# drvinput0.net
KiCad netlist of a schematic drawn in Altium Designer
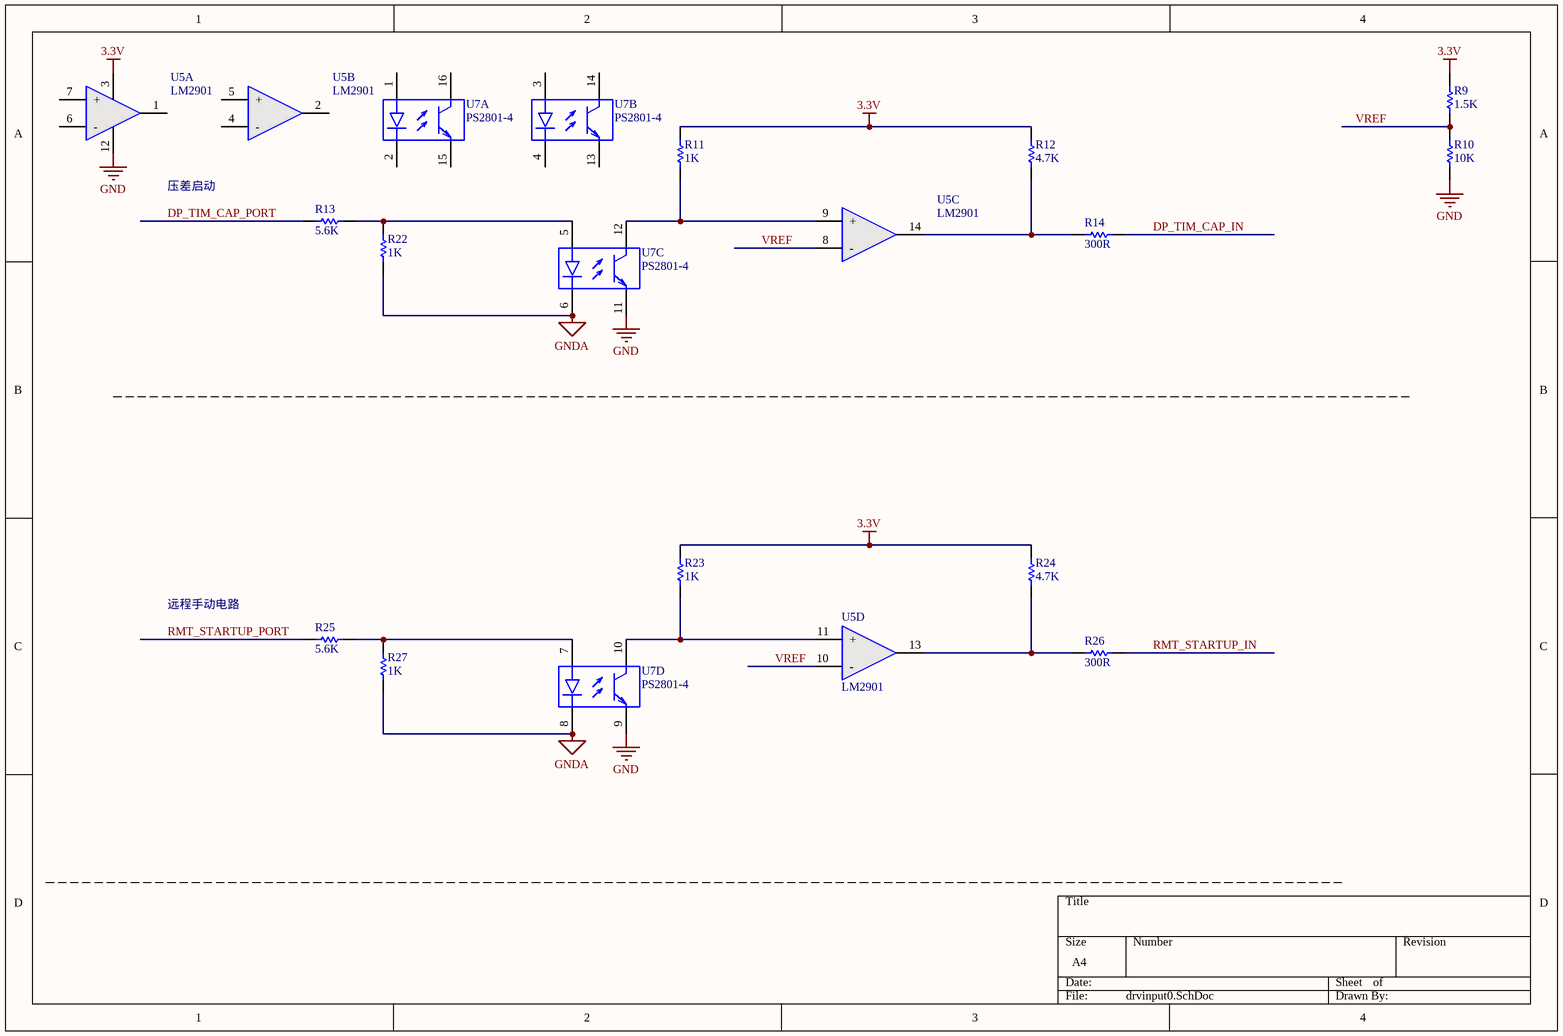
[diagram p0: drvinput0.SchDoc]

(export (version "E")
  (design (tool "Eeschema 10.0.6"))
  (components
    (comp (ref "R9")
      (value "1.5K")
      (footprint "RESC2012M")
      (description "Resistor")
      (fields (field (name "PUBLISHER") "Altium Limited"))
      (libsource (lib "Miscellaneous Devices") (part "Res1"))
    )
    (comp (ref "R10")
      (value "10K")
      (footprint "RESC2012M")
      (description "Resistor")
      (fields (field (name "PUBLISHER") "Altium Limited"))
      (libsource (lib "Miscellaneous Devices") (part "Res1"))
    )
    (comp (ref "R11")
      (value "1K")
      (footprint "RESC2012M")
      (description "Resistor")
      (fields (field (name "PUBLISHER") "Altium Limited"))
      (libsource (lib "Miscellaneous Devices") (part "Res1"))
    )
    (comp (ref "R12")
      (value "4.7K")
      (footprint "RESC2012M")
      (description "Resistor")
      (fields (field (name "PUBLISHER") "Altium Limited"))
      (libsource (lib "Miscellaneous Devices") (part "Res1"))
    )
    (comp (ref "R13")
      (value "5.6K")
      (footprint "RESC2012M")
      (description "Resistor")
      (fields (field (name "PUBLISHER") "Altium Limited"))
      (libsource (lib "Miscellaneous Devices") (part "Res1"))
    )
    (comp (ref "R14")
      (value "300R")
      (footprint "RESC2012M")
      (description "Resistor")
      (fields (field (name "PUBLISHER") "Altium Limited"))
      (libsource (lib "Miscellaneous Devices") (part "Res1"))
    )
    (comp (ref "R22")
      (value "1K")
      (footprint "RESC2012M")
      (description "Resistor")
      (fields (field (name "PUBLISHER") "Altium Limited"))
      (libsource (lib "Miscellaneous Devices") (part "Res1"))
    )
    (comp (ref "R23")
      (value "1K")
      (footprint "RESC2012M")
      (description "Resistor")
      (fields (field (name "PUBLISHER") "Altium Limited"))
      (libsource (lib "Miscellaneous Devices") (part "Res1"))
    )
    (comp (ref "R24")
      (value "4.7K")
      (footprint "RESC2012M")
      (description "Resistor")
      (fields (field (name "PUBLISHER") "Altium Limited"))
      (libsource (lib "Miscellaneous Devices") (part "Res1"))
    )
    (comp (ref "R25")
      (value "5.6K")
      (footprint "RESC2012M")
      (description "Resistor")
      (fields (field (name "PUBLISHER") "Altium Limited"))
      (libsource (lib "Miscellaneous Devices") (part "Res1"))
    )
    (comp (ref "R26")
      (value "300R")
      (footprint "RESC2012M")
      (description "Resistor")
      (fields (field (name "PUBLISHER") "Altium Limited"))
      (libsource (lib "Miscellaneous Devices") (part "Res1"))
    )
    (comp (ref "R27")
      (value "1K")
      (footprint "RESC2012M")
      (description "Resistor")
      (fields (field (name "PUBLISHER") "Altium Limited"))
      (libsource (lib "Miscellaneous Devices") (part "Res1"))
    )
    (comp (ref "U5")
      (value "LM2901")
      (footprint "SOIC-14AM")
      (description "4通道差分比较器芯片")
      (libsource (lib "UserSchDev") (part "LM2901"))
    )
    (comp (ref "U7")
      (value "PS2801-4")
      (footprint "SOIC16_N")
      (fields (field (name "PUBLISHER") "Altium Limited"))
      (libsource (lib "UserSchDev") (part "PS2801-4"))
    )
  )
  (nets
    (net (code "1") (name "/DP_TIM_CAP_IN") (class "Default")
      (node (ref "R14") (pin "1") (pinfunction "1_1") (pintype "passive"))
    )
    (net (code "2") (name "/DP_TIM_CAP_PORT") (class "Default")
      (node (ref "R13") (pin "2") (pinfunction "2_2") (pintype "passive"))
    )
    (net (code "3") (name "/RMT_STARTUP_IN") (class "Default")
      (node (ref "R26") (pin "2") (pinfunction "2_2") (pintype "passive"))
    )
    (net (code "4") (name "/RMT_STARTUP_PORT") (class "Default")
      (node (ref "R25") (pin "2") (pinfunction "2_2") (pintype "passive"))
    )
    (net (code "5") (name "/VREF") (class "Default")
      (node (ref "R10") (pin "1") (pinfunction "1_1") (pintype "passive"))
      (node (ref "R9") (pin "2") (pinfunction "2_2") (pintype "passive"))
      (node (ref "U5") (pin "10") (pinfunction "-_10") (pintype "passive"))
      (node (ref "U5") (pin "8") (pinfunction "-_8") (pintype "passive"))
    )
    (net (code "6") (name "3.3V") (class "Default")
      (node (ref "R11") (pin "1") (pinfunction "1_1") (pintype "passive"))
      (node (ref "R12") (pin "2") (pinfunction "2_2") (pintype "passive"))
      (node (ref "R23") (pin "1") (pinfunction "1_1") (pintype "passive"))
      (node (ref "R24") (pin "2") (pinfunction "2_2") (pintype "passive"))
      (node (ref "R9") (pin "1") (pinfunction "1_1") (pintype "passive"))
      (node (ref "U5") (pin "3") (pinfunction "V+_3") (pintype "power_in"))
    )
    (net (code "7") (name "GND") (class "Default")
      (node (ref "R10") (pin "2") (pinfunction "2_2") (pintype "passive"))
      (node (ref "U5") (pin "12") (pinfunction "V-_12") (pintype "power_in"))
      (node (ref "U7") (pin "11") (pinfunction "E_11") (pintype "passive"))
      (node (ref "U7") (pin "9") (pinfunction "E_9") (pintype "passive"))
    )
    (net (code "8") (name "GNDA") (class "Default")
      (node (ref "R22") (pin "1") (pinfunction "1_1") (pintype "passive"))
      (node (ref "R27") (pin "1") (pinfunction "1_1") (pintype "passive"))
      (node (ref "U7") (pin "6") (pinfunction "-_6") (pintype "passive"))
      (node (ref "U7") (pin "8") (pinfunction "-_8") (pintype "passive"))
    )
    (net (code "9") (name "Net-(U5C-+)") (class "Default")
      (node (ref "R11") (pin "2") (pinfunction "2_2") (pintype "passive"))
      (node (ref "U5") (pin "9") (pinfunction "+_9") (pintype "passive"))
      (node (ref "U7") (pin "12") (pinfunction "C_12") (pintype "passive"))
    )
    (net (code "10") (name "Net-(U5C-OUT)") (class "Default")
      (node (ref "R12") (pin "1") (pinfunction "1_1") (pintype "passive"))
      (node (ref "R14") (pin "2") (pinfunction "2_2") (pintype "passive"))
      (node (ref "U5") (pin "14") (pinfunction "OUT_14") (pintype "passive"))
    )
    (net (code "11") (name "Net-(U5D-+)") (class "Default")
      (node (ref "R23") (pin "2") (pinfunction "2_2") (pintype "passive"))
      (node (ref "U5") (pin "11") (pinfunction "+_11") (pintype "passive"))
      (node (ref "U7") (pin "10") (pinfunction "C_10") (pintype "passive"))
    )
    (net (code "12") (name "Net-(U5D-OUT)") (class "Default")
      (node (ref "R24") (pin "1") (pinfunction "1_1") (pintype "passive"))
      (node (ref "R26") (pin "1") (pinfunction "1_1") (pintype "passive"))
      (node (ref "U5") (pin "13") (pinfunction "OUT_13") (pintype "passive"))
    )
    (net (code "13") (name "Net-(U7C-+)") (class "Default")
      (node (ref "R13") (pin "1") (pinfunction "1_1") (pintype "passive"))
      (node (ref "R22") (pin "2") (pinfunction "2_2") (pintype "passive"))
      (node (ref "U7") (pin "5") (pinfunction "+_5") (pintype "passive"))
    )
    (net (code "14") (name "Net-(U7D-+)") (class "Default")
      (node (ref "R25") (pin "1") (pinfunction "1_1") (pintype "passive"))
      (node (ref "R27") (pin "2") (pinfunction "2_2") (pintype "passive"))
      (node (ref "U7") (pin "7") (pinfunction "+_7") (pintype "passive"))
    )
    (net (code "15") (name "unconnected-(U5A-+-Pad7)") (class "Default")
      (node (ref "U5") (pin "7") (pinfunction "+_7") (pintype "passive"))
    )
    (net (code "16") (name "unconnected-(U5A---Pad6)") (class "Default")
      (node (ref "U5") (pin "6") (pinfunction "-_6") (pintype "passive"))
    )
    (net (code "17") (name "unconnected-(U5A-OUT-Pad1)") (class "Default")
      (node (ref "U5") (pin "1") (pinfunction "OUT_1") (pintype "passive"))
    )
    (net (code "18") (name "unconnected-(U5B-+-Pad5)") (class "Default")
      (node (ref "U5") (pin "5") (pinfunction "+_5") (pintype "passive"))
    )
    (net (code "19") (name "unconnected-(U5B---Pad4)") (class "Default")
      (node (ref "U5") (pin "4") (pinfunction "-_4") (pintype "passive"))
    )
    (net (code "20") (name "unconnected-(U5B-OUT-Pad2)") (class "Default")
      (node (ref "U5") (pin "2") (pinfunction "OUT_2") (pintype "passive"))
    )
    (net (code "21") (name "unconnected-(U7A-+-Pad1)") (class "Default")
      (node (ref "U7") (pin "1") (pinfunction "+_1") (pintype "passive"))
    )
    (net (code "22") (name "unconnected-(U7A---Pad2)") (class "Default")
      (node (ref "U7") (pin "2") (pinfunction "-_2") (pintype "passive"))
    )
    (net (code "23") (name "unconnected-(U7A-C-Pad16)") (class "Default")
      (node (ref "U7") (pin "16") (pinfunction "C_16") (pintype "passive"))
    )
    (net (code "24") (name "unconnected-(U7A-E-Pad15)") (class "Default")
      (node (ref "U7") (pin "15") (pinfunction "E_15") (pintype "passive"))
    )
    (net (code "25") (name "unconnected-(U7B-+-Pad3)") (class "Default")
      (node (ref "U7") (pin "3") (pinfunction "+_3") (pintype "passive"))
    )
    (net (code "26") (name "unconnected-(U7B---Pad4)") (class "Default")
      (node (ref "U7") (pin "4") (pinfunction "-_4") (pintype "passive"))
    )
    (net (code "27") (name "unconnected-(U7B-C-Pad14)") (class "Default")
      (node (ref "U7") (pin "14") (pinfunction "C_14") (pintype "passive"))
    )
    (net (code "28") (name "unconnected-(U7B-E-Pad13)") (class "Default")
      (node (ref "U7") (pin "13") (pinfunction "E_13") (pintype "passive"))
    )
  )
)
